# Projet_4A.net
KiCad netlist of a schematic drawn in EAGLE
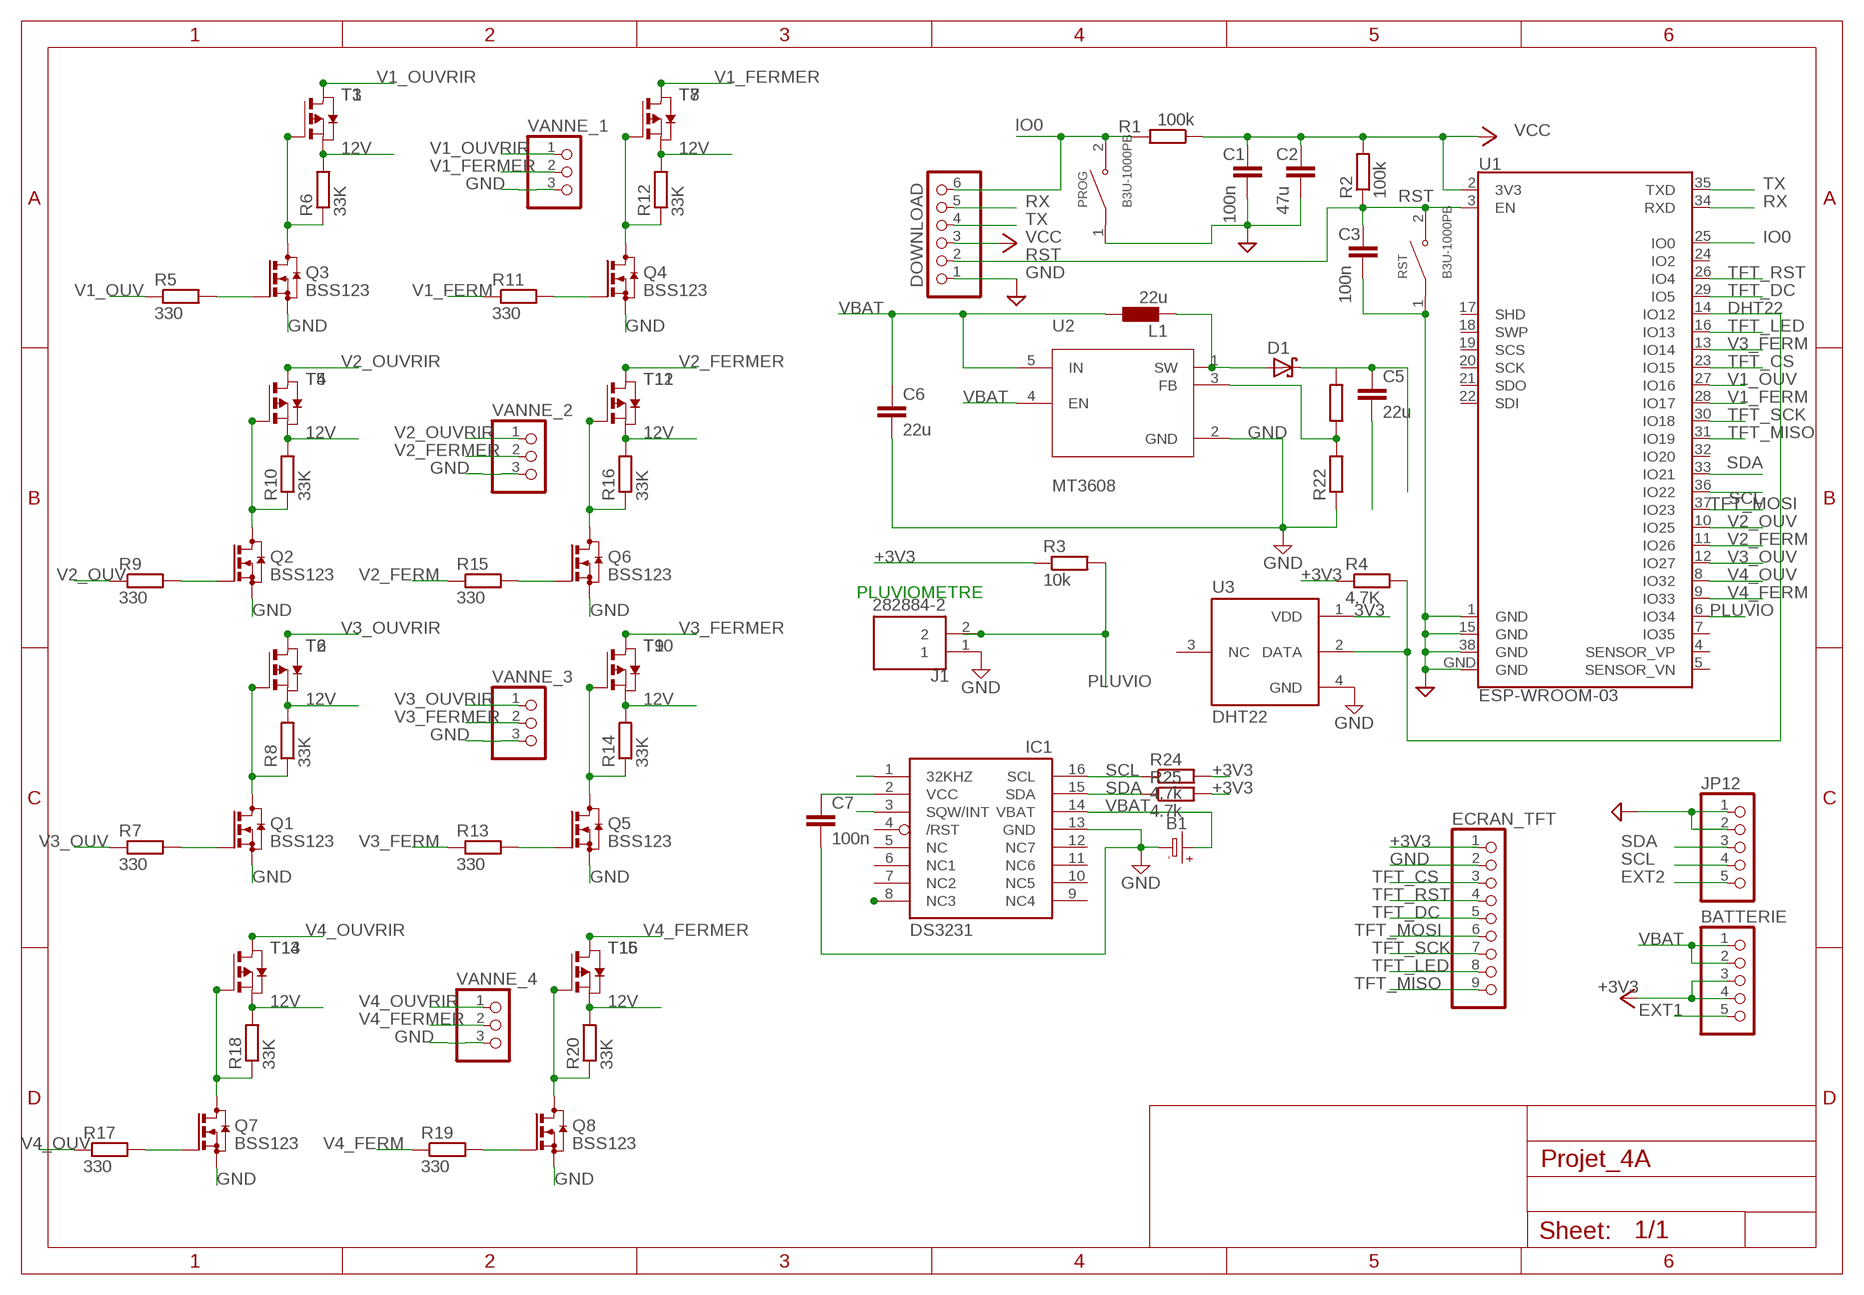
[diagram p0: schematic, sheet 1]

(export (version "E")
  (design (tool "Eeschema 10.0.6"))
  (components
    (comp (ref "B1")
      (value "BATTERYCR2032_BAT-HLD-001")
      (footprint "eagle-import:CR2032_SMT_BAT-HLD-001")
      (libsource (lib "eagle-import") (part "BATTERYCR2032_BAT-HLD-001"))
    )
    (comp (ref "BATTERIE")
      (value "PINHD-1X5S")
      (footprint "eagle-import:1X05S")
      (libsource (lib "eagle-import") (part "PINHD-1X5S"))
    )
    (comp (ref "C1")
      (value "100n")
      (footprint "eagle-import:C0805")
      (libsource (lib "eagle-import") (part "C"))
    )
    (comp (ref "C2")
      (value "47u")
      (footprint "eagle-import:C0805")
      (libsource (lib "eagle-import") (part "C"))
    )
    (comp (ref "C3")
      (value "100n")
      (footprint "eagle-import:C0805")
      (libsource (lib "eagle-import") (part "C"))
    )
    (comp (ref "C5")
      (value "22u")
      (footprint "eagle-import:C0805")
      (libsource (lib "eagle-import") (part "C"))
    )
    (comp (ref "C6")
      (value "22u")
      (footprint "eagle-import:C0805")
      (libsource (lib "eagle-import") (part "C"))
    )
    (comp (ref "C7")
      (value "100n")
      (footprint "eagle-import:C0805")
      (libsource (lib "eagle-import") (part "C"))
    )
    (comp (ref "D1")
      (value "SCHOTTKY-DIODEAG")
      (footprint "eagle-import:AG")
      (libsource (lib "eagle-import") (part "SCHOTTKY-DIODEAG"))
    )
    (comp (ref "DOWNLOAD")
      (value "PINHD-1X6S")
      (footprint "eagle-import:1X06S")
      (libsource (lib "eagle-import") (part "PINHD-1X6S"))
    )
    (comp (ref "ECRAN_TFT")
      (value "PINHD-1X9")
      (footprint "eagle-import:1X09")
      (libsource (lib "eagle-import") (part "PINHD-1X9"))
    )
    (comp (ref "IC1")
      (value "DS3231/SO")
      (footprint "eagle-import:SO16W")
      (fields (field (name "MF") "Analog Devices") (field (name "MP") "DS3231"))
      (libsource (lib "eagle-import") (part "DS3231/SO"))
    )
    (comp (ref "J1")
      (value "282884-2")
      (footprint "eagle-import:TE_282884-2")
      (fields (field (name "MF") "TE Connectivity"))
      (libsource (lib "eagle-import") (part "282884-2"))
    )
    (comp (ref "JP12")
      (value "PINHD-1X5S")
      (footprint "eagle-import:1X05S")
      (libsource (lib "eagle-import") (part "PINHD-1X5S"))
    )
    (comp (ref "L1")
      (value "22u")
      (footprint "eagle-import:0204_7")
      (libsource (lib "eagle-import") (part "L0204/7"))
    )
    (comp (ref "PROG")
      (value "B3U-1000PB")
      (footprint "eagle-import:SW_B3U-1000PB")
      (libsource (lib "eagle-import") (part "B3U-1000PB"))
    )
    (comp (ref "Q1")
      (value "BSS123")
      (footprint "eagle-import:SOT23")
      (libsource (lib "eagle-import") (part "BSS123"))
    )
    (comp (ref "Q2")
      (value "BSS123")
      (footprint "eagle-import:SOT23")
      (libsource (lib "eagle-import") (part "BSS123"))
    )
    (comp (ref "Q3")
      (value "BSS123")
      (footprint "eagle-import:SOT23")
      (libsource (lib "eagle-import") (part "BSS123"))
    )
    (comp (ref "Q4")
      (value "BSS123")
      (footprint "eagle-import:SOT23")
      (libsource (lib "eagle-import") (part "BSS123"))
    )
    (comp (ref "Q5")
      (value "BSS123")
      (footprint "eagle-import:SOT23")
      (libsource (lib "eagle-import") (part "BSS123"))
    )
    (comp (ref "Q6")
      (value "BSS123")
      (footprint "eagle-import:SOT23")
      (libsource (lib "eagle-import") (part "BSS123"))
    )
    (comp (ref "Q7")
      (value "BSS123")
      (footprint "eagle-import:SOT23")
      (libsource (lib "eagle-import") (part "BSS123"))
    )
    (comp (ref "Q8")
      (value "BSS123")
      (footprint "eagle-import:SOT23")
      (libsource (lib "eagle-import") (part "BSS123"))
    )
    (comp (ref "R1")
      (value "100k")
      (footprint "eagle-import:R1206")
      (libsource (lib "eagle-import") (part "RR1206"))
    )
    (comp (ref "R2")
      (value "100k")
      (footprint "eagle-import:R1206")
      (libsource (lib "eagle-import") (part "RR1206"))
    )
    (comp (ref "R3")
      (value "10k")
      (footprint "eagle-import:R0805")
      (libsource (lib "eagle-import") (part "R-EU_R0805"))
    )
    (comp (ref "R4")
      (value "4,7K")
      (footprint "eagle-import:0207_10")
      (libsource (lib "eagle-import") (part "R-EU_0207/10"))
    )
    (comp (ref "R5")
      (value "330")
      (footprint "eagle-import:0207_10")
      (libsource (lib "eagle-import") (part "R-EU_0207/10"))
    )
    (comp (ref "R6")
      (value "33K")
      (footprint "eagle-import:0207_10")
      (libsource (lib "eagle-import") (part "R-EU_0207/10"))
    )
    (comp (ref "R7")
      (value "330")
      (footprint "eagle-import:0207_10")
      (libsource (lib "eagle-import") (part "R-EU_0207/10"))
    )
    (comp (ref "R8")
      (value "33K")
      (footprint "eagle-import:0207_10")
      (libsource (lib "eagle-import") (part "R-EU_0207/10"))
    )
    (comp (ref "R9")
      (value "330")
      (footprint "eagle-import:0207_10")
      (libsource (lib "eagle-import") (part "R-EU_0207/10"))
    )
    (comp (ref "R10")
      (value "33K")
      (footprint "eagle-import:0207_10")
      (libsource (lib "eagle-import") (part "R-EU_0207/10"))
    )
    (comp (ref "R11")
      (value "330")
      (footprint "eagle-import:0207_10")
      (libsource (lib "eagle-import") (part "R-EU_0207/10"))
    )
    (comp (ref "R12")
      (value "33K")
      (footprint "eagle-import:0207_10")
      (libsource (lib "eagle-import") (part "R-EU_0207/10"))
    )
    (comp (ref "R13")
      (value "330")
      (footprint "eagle-import:0207_10")
      (libsource (lib "eagle-import") (part "R-EU_0207/10"))
    )
    (comp (ref "R14")
      (value "33K")
      (footprint "eagle-import:0207_10")
      (libsource (lib "eagle-import") (part "R-EU_0207/10"))
    )
    (comp (ref "R15")
      (value "330")
      (footprint "eagle-import:0207_10")
      (libsource (lib "eagle-import") (part "R-EU_0207/10"))
    )
    (comp (ref "R16")
      (value "33K")
      (footprint "eagle-import:0207_10")
      (libsource (lib "eagle-import") (part "R-EU_0207/10"))
    )
    (comp (ref "R17")
      (value "330")
      (footprint "eagle-import:0207_10")
      (libsource (lib "eagle-import") (part "R-EU_0207/10"))
    )
    (comp (ref "R18")
      (value "33K")
      (footprint "eagle-import:0207_10")
      (libsource (lib "eagle-import") (part "R-EU_0207/10"))
    )
    (comp (ref "R19")
      (value "330")
      (footprint "eagle-import:0207_10")
      (libsource (lib "eagle-import") (part "R-EU_0207/10"))
    )
    (comp (ref "R20")
      (value "33K")
      (footprint "eagle-import:0207_10")
      (libsource (lib "eagle-import") (part "R-EU_0207/10"))
    )
    (comp (ref "R22")
      (value "R-EU_0204/2V")
      (footprint "eagle-import:0204V")
      (libsource (lib "eagle-import") (part "R-EU_0204/2V"))
    )
    (comp (ref "R24")
      (value "4,7k")
      (footprint "eagle-import:0204V")
      (libsource (lib "eagle-import") (part "R-EU_0204/2V"))
    )
    (comp (ref "R25")
      (value "4.7k")
      (footprint "eagle-import:0204V")
      (libsource (lib "eagle-import") (part "R-EU_0204/2V"))
    )
    (comp (ref "RST")
      (value "B3U-1000PB")
      (footprint "eagle-import:SW_B3U-1000PB")
      (libsource (lib "eagle-import") (part "B3U-1000PB"))
    )
    (comp (ref "T1")
      (value "PMOSSOT23")
      (footprint "eagle-import:SOT-23")
      (libsource (lib "eagle-import") (part "PMOSSOT23"))
    )
    (comp (ref "T2")
      (value "PMOSSOT23")
      (footprint "eagle-import:SOT-23")
      (libsource (lib "eagle-import") (part "PMOSSOT23"))
    )
    (comp (ref "T3")
      (value "PMOSSOT23")
      (footprint "eagle-import:SOT-23")
      (libsource (lib "eagle-import") (part "PMOSSOT23"))
    )
    (comp (ref "T4")
      (value "PMOSSOT23")
      (footprint "eagle-import:SOT-23")
      (libsource (lib "eagle-import") (part "PMOSSOT23"))
    )
    (comp (ref "T5")
      (value "PMOSSOT23")
      (footprint "eagle-import:SOT-23")
      (libsource (lib "eagle-import") (part "PMOSSOT23"))
    )
    (comp (ref "T6")
      (value "PMOSSOT23")
      (footprint "eagle-import:SOT-23")
      (libsource (lib "eagle-import") (part "PMOSSOT23"))
    )
    (comp (ref "T7")
      (value "PMOSSOT23")
      (footprint "eagle-import:SOT-23")
      (libsource (lib "eagle-import") (part "PMOSSOT23"))
    )
    (comp (ref "T8")
      (value "PMOSSOT23")
      (footprint "eagle-import:SOT-23")
      (libsource (lib "eagle-import") (part "PMOSSOT23"))
    )
    (comp (ref "T9")
      (value "PMOSSOT23")
      (footprint "eagle-import:SOT-23")
      (libsource (lib "eagle-import") (part "PMOSSOT23"))
    )
    (comp (ref "T10")
      (value "PMOSSOT23")
      (footprint "eagle-import:SOT-23")
      (libsource (lib "eagle-import") (part "PMOSSOT23"))
    )
    (comp (ref "T11")
      (value "PMOSSOT23")
      (footprint "eagle-import:SOT-23")
      (libsource (lib "eagle-import") (part "PMOSSOT23"))
    )
    (comp (ref "T12")
      (value "PMOSSOT23")
      (footprint "eagle-import:SOT-23")
      (libsource (lib "eagle-import") (part "PMOSSOT23"))
    )
    (comp (ref "T13")
      (value "PMOSSOT23")
      (footprint "eagle-import:SOT-23")
      (libsource (lib "eagle-import") (part "PMOSSOT23"))
    )
    (comp (ref "T14")
      (value "PMOSSOT23")
      (footprint "eagle-import:SOT-23")
      (libsource (lib "eagle-import") (part "PMOSSOT23"))
    )
    (comp (ref "T15")
      (value "PMOSSOT23")
      (footprint "eagle-import:SOT-23")
      (libsource (lib "eagle-import") (part "PMOSSOT23"))
    )
    (comp (ref "T16")
      (value "PMOSSOT23")
      (footprint "eagle-import:SOT-23")
      (libsource (lib "eagle-import") (part "PMOSSOT23"))
    )
    (comp (ref "U1")
      (value "ESP-WROOM-03")
      (footprint "eagle-import:ESP-WROOM-03")
      (libsource (lib "eagle-import") (part "ESP-WROOM-03"))
    )
    (comp (ref "U2")
      (value "MT3608")
      (footprint "eagle-import:SOT95P280X145-6N")
      (fields (field (name "MANUFACTURER") "Aero Semi"))
      (libsource (lib "eagle-import") (part "MT3608"))
    )
    (comp (ref "U3")
      (value "DHT22")
      (footprint "eagle-import:XDCR_DHT22")
      (fields (field (name "MF") "Aosong Electronics"))
      (libsource (lib "eagle-import") (part "DHT22"))
    )
    (comp (ref "VANNE_1")
      (value "PINHD-1X3")
      (footprint "eagle-import:1X03")
      (libsource (lib "eagle-import") (part "PINHD-1X3"))
    )
    (comp (ref "VANNE_2")
      (value "PINHD-1X3")
      (footprint "eagle-import:1X03")
      (libsource (lib "eagle-import") (part "PINHD-1X3"))
    )
    (comp (ref "VANNE_3")
      (value "PINHD-1X3")
      (footprint "eagle-import:1X03")
      (libsource (lib "eagle-import") (part "PINHD-1X3"))
    )
    (comp (ref "VANNE_4")
      (value "PINHD-1X3")
      (footprint "eagle-import:1X03")
      (libsource (lib "eagle-import") (part "PINHD-1X3"))
    )
  )
  (nets
    (net (code "1") (name "+3V3") (class "Default")
      (node (ref "BATTERIE") (pin "3") (pinfunction "3_3") (pintype "passive"))
      (node (ref "BATTERIE") (pin "4") (pinfunction "4_4") (pintype "passive"))
      (node (ref "C7") (pin "1") (pinfunction "1_1") (pintype "passive"))
      (node (ref "ECRAN_TFT") (pin "1") (pinfunction "1_1") (pintype "passive"))
      (node (ref "IC1") (pin "2") (pinfunction "VCC_2") (pintype "power_in"))
      (node (ref "R24") (pin "2") (pinfunction "2_2") (pintype "passive"))
      (node (ref "R25") (pin "2") (pinfunction "2_2") (pintype "passive"))
      (node (ref "R3") (pin "1") (pinfunction "1_1") (pintype "passive"))
      (node (ref "R4") (pin "1") (pinfunction "1_1") (pintype "passive"))
    )
    (net (code "2") (name "/3V3") (class "Default")
      (node (ref "U3") (pin "1") (pinfunction "VDD_1") (pintype "power_in"))
    )
    (net (code "3") (name "/12V") (class "Default")
      (node (ref "C5") (pin "1") (pinfunction "1_1") (pintype "passive"))
      (node (ref "D1") (pin "C") (pinfunction "C_C") (pintype "passive"))
      (node (ref "R10") (pin "2") (pinfunction "2_2") (pintype "passive"))
      (node (ref "R12") (pin "2") (pinfunction "2_2") (pintype "passive"))
      (node (ref "R14") (pin "2") (pinfunction "2_2") (pintype "passive"))
      (node (ref "R16") (pin "2") (pinfunction "2_2") (pintype "passive"))
      (node (ref "R18") (pin "2") (pinfunction "2_2") (pintype "passive"))
      (node (ref "R20") (pin "2") (pinfunction "2_2") (pintype "passive"))
      (node (ref "R6") (pin "2") (pinfunction "2_2") (pintype "passive"))
      (node (ref "R8") (pin "2") (pinfunction "2_2") (pintype "passive"))
      (node (ref "T1") (pin "2") (pinfunction "S_2") (pintype "passive"))
      (node (ref "T10") (pin "2") (pinfunction "S_2") (pintype "passive"))
      (node (ref "T11") (pin "2") (pinfunction "S_2") (pintype "passive"))
      (node (ref "T12") (pin "2") (pinfunction "S_2") (pintype "passive"))
      (node (ref "T13") (pin "2") (pinfunction "S_2") (pintype "passive"))
      (node (ref "T14") (pin "2") (pinfunction "S_2") (pintype "passive"))
      (node (ref "T15") (pin "2") (pinfunction "S_2") (pintype "passive"))
      (node (ref "T16") (pin "2") (pinfunction "S_2") (pintype "passive"))
      (node (ref "T2") (pin "2") (pinfunction "S_2") (pintype "passive"))
      (node (ref "T3") (pin "2") (pinfunction "S_2") (pintype "passive"))
      (node (ref "T4") (pin "2") (pinfunction "S_2") (pintype "passive"))
      (node (ref "T5") (pin "2") (pinfunction "S_2") (pintype "passive"))
      (node (ref "T6") (pin "2") (pinfunction "S_2") (pintype "passive"))
      (node (ref "T7") (pin "2") (pinfunction "S_2") (pintype "passive"))
      (node (ref "T8") (pin "2") (pinfunction "S_2") (pintype "passive"))
      (node (ref "T9") (pin "2") (pinfunction "S_2") (pintype "passive"))
    )
    (net (code "4") (name "/DHT22") (class "Default")
      (node (ref "R4") (pin "2") (pinfunction "2_2") (pintype "passive"))
      (node (ref "U1") (pin "14") (pinfunction "IO12_14") (pintype "bidirectional"))
      (node (ref "U3") (pin "2") (pinfunction "DATA_2") (pintype "bidirectional"))
    )
    (net (code "5") (name "/EXT1") (class "Default")
      (node (ref "BATTERIE") (pin "5") (pinfunction "5_5") (pintype "passive"))
    )
    (net (code "6") (name "/EXT2") (class "Default")
      (node (ref "JP12") (pin "5") (pinfunction "5_5") (pintype "passive"))
    )
    (net (code "7") (name "/IO0") (class "Default")
      (node (ref "DOWNLOAD") (pin "6") (pinfunction "6_6") (pintype "passive"))
      (node (ref "PROG") (pin "2") (pinfunction "2_2") (pintype "passive"))
      (node (ref "R1") (pin "2") (pinfunction "2_2") (pintype "passive"))
      (node (ref "U1") (pin "25") (pinfunction "IO0_25") (pintype "bidirectional"))
    )
    (net (code "8") (name "/PLUVIO") (class "Default")
      (node (ref "J1") (pin "2") (pinfunction "2_2") (pintype "passive"))
      (node (ref "R3") (pin "2") (pinfunction "2_2") (pintype "passive"))
      (node (ref "U1") (pin "6") (pinfunction "IO34_6") (pintype "bidirectional"))
    )
    (net (code "9") (name "/RST") (class "Default")
      (node (ref "C3") (pin "1") (pinfunction "1_1") (pintype "passive"))
      (node (ref "DOWNLOAD") (pin "2") (pinfunction "2_2") (pintype "passive"))
      (node (ref "R2") (pin "1") (pinfunction "1_1") (pintype "passive"))
      (node (ref "RST") (pin "2") (pinfunction "2_2") (pintype "passive"))
      (node (ref "U1") (pin "3") (pinfunction "EN_3") (pintype "bidirectional"))
    )
    (net (code "10") (name "/RX") (class "Default")
      (node (ref "DOWNLOAD") (pin "5") (pinfunction "5_5") (pintype "passive"))
      (node (ref "U1") (pin "34") (pinfunction "RXD_34") (pintype "bidirectional"))
    )
    (net (code "11") (name "/SCL") (class "Default")
      (node (ref "IC1") (pin "16") (pinfunction "SCL_16") (pintype "bidirectional"))
      (node (ref "JP12") (pin "4") (pinfunction "4_4") (pintype "passive"))
      (node (ref "R24") (pin "1") (pinfunction "1_1") (pintype "passive"))
      (node (ref "U1") (pin "36") (pinfunction "IO22_36") (pintype "bidirectional"))
    )
    (net (code "12") (name "/SDA") (class "Default")
      (node (ref "IC1") (pin "15") (pinfunction "SDA_15") (pintype "bidirectional"))
      (node (ref "JP12") (pin "3") (pinfunction "3_3") (pintype "passive"))
      (node (ref "R25") (pin "1") (pinfunction "1_1") (pintype "passive"))
      (node (ref "U1") (pin "33") (pinfunction "IO21_33") (pintype "bidirectional"))
    )
    (net (code "13") (name "/TFT_CS") (class "Default")
      (node (ref "ECRAN_TFT") (pin "3") (pinfunction "3_3") (pintype "passive"))
      (node (ref "U1") (pin "23") (pinfunction "IO15_23") (pintype "bidirectional"))
    )
    (net (code "14") (name "/TFT_DC") (class "Default")
      (node (ref "ECRAN_TFT") (pin "5") (pinfunction "5_5") (pintype "passive"))
      (node (ref "U1") (pin "29") (pinfunction "IO5_29") (pintype "bidirectional"))
    )
    (net (code "15") (name "/TFT_LED") (class "Default")
      (node (ref "ECRAN_TFT") (pin "8") (pinfunction "8_8") (pintype "passive"))
      (node (ref "U1") (pin "16") (pinfunction "IO13_16") (pintype "bidirectional"))
    )
    (net (code "16") (name "/TFT_MISO") (class "Default")
      (node (ref "ECRAN_TFT") (pin "9") (pinfunction "9_9") (pintype "passive"))
      (node (ref "U1") (pin "31") (pinfunction "IO19_31") (pintype "bidirectional"))
    )
    (net (code "17") (name "/TFT_MOSI") (class "Default")
      (node (ref "ECRAN_TFT") (pin "6") (pinfunction "6_6") (pintype "passive"))
      (node (ref "U1") (pin "37") (pinfunction "IO23_37") (pintype "bidirectional"))
    )
    (net (code "18") (name "/TFT_RST") (class "Default")
      (node (ref "ECRAN_TFT") (pin "4") (pinfunction "4_4") (pintype "passive"))
      (node (ref "U1") (pin "26") (pinfunction "IO4_26") (pintype "bidirectional"))
    )
    (net (code "19") (name "/TFT_SCK") (class "Default")
      (node (ref "ECRAN_TFT") (pin "7") (pinfunction "7_7") (pintype "passive"))
      (node (ref "U1") (pin "30") (pinfunction "IO18_30") (pintype "bidirectional"))
    )
    (net (code "20") (name "/TX") (class "Default")
      (node (ref "DOWNLOAD") (pin "4") (pinfunction "4_4") (pintype "passive"))
      (node (ref "U1") (pin "35") (pinfunction "TXD_35") (pintype "bidirectional"))
    )
    (net (code "21") (name "/V1_FERM") (class "Default")
      (node (ref "R11") (pin "1") (pinfunction "1_1") (pintype "passive"))
      (node (ref "U1") (pin "28") (pinfunction "IO17_28") (pintype "bidirectional"))
    )
    (net (code "22") (name "/V1_FERMER") (class "Default")
      (node (ref "T7") (pin "1") (pinfunction "D_1") (pintype "passive"))
      (node (ref "T8") (pin "1") (pinfunction "D_1") (pintype "passive"))
      (node (ref "VANNE_1") (pin "2") (pinfunction "2_2") (pintype "passive"))
    )
    (net (code "23") (name "/V1_OUV") (class "Default")
      (node (ref "R5") (pin "1") (pinfunction "1_1") (pintype "passive"))
      (node (ref "U1") (pin "27") (pinfunction "IO16_27") (pintype "bidirectional"))
    )
    (net (code "24") (name "/V1_OUVRIR") (class "Default")
      (node (ref "T1") (pin "1") (pinfunction "D_1") (pintype "passive"))
      (node (ref "T3") (pin "1") (pinfunction "D_1") (pintype "passive"))
      (node (ref "VANNE_1") (pin "1") (pinfunction "1_1") (pintype "passive"))
    )
    (net (code "25") (name "/V2_FERM") (class "Default")
      (node (ref "R15") (pin "1") (pinfunction "1_1") (pintype "passive"))
      (node (ref "U1") (pin "11") (pinfunction "IO26_11") (pintype "bidirectional"))
    )
    (net (code "26") (name "/V2_FERMER") (class "Default")
      (node (ref "T11") (pin "1") (pinfunction "D_1") (pintype "passive"))
      (node (ref "T12") (pin "1") (pinfunction "D_1") (pintype "passive"))
      (node (ref "VANNE_2") (pin "2") (pinfunction "2_2") (pintype "passive"))
    )
    (net (code "27") (name "/V2_OUV") (class "Default")
      (node (ref "R9") (pin "1") (pinfunction "1_1") (pintype "passive"))
      (node (ref "U1") (pin "10") (pinfunction "IO25_10") (pintype "bidirectional"))
    )
    (net (code "28") (name "/V2_OUVRIR") (class "Default")
      (node (ref "T4") (pin "1") (pinfunction "D_1") (pintype "passive"))
      (node (ref "T5") (pin "1") (pinfunction "D_1") (pintype "passive"))
      (node (ref "VANNE_2") (pin "1") (pinfunction "1_1") (pintype "passive"))
    )
    (net (code "29") (name "/V3_FERM") (class "Default")
      (node (ref "R13") (pin "1") (pinfunction "1_1") (pintype "passive"))
      (node (ref "U1") (pin "13") (pinfunction "IO14_13") (pintype "bidirectional"))
    )
    (net (code "30") (name "/V3_FERMER") (class "Default")
      (node (ref "T10") (pin "1") (pinfunction "D_1") (pintype "passive"))
      (node (ref "T9") (pin "1") (pinfunction "D_1") (pintype "passive"))
      (node (ref "VANNE_3") (pin "2") (pinfunction "2_2") (pintype "passive"))
    )
    (net (code "31") (name "/V3_OUV") (class "Default")
      (node (ref "R7") (pin "1") (pinfunction "1_1") (pintype "passive"))
      (node (ref "U1") (pin "12") (pinfunction "IO27_12") (pintype "bidirectional"))
    )
    (net (code "32") (name "/V3_OUVRIR") (class "Default")
      (node (ref "T2") (pin "1") (pinfunction "D_1") (pintype "passive"))
      (node (ref "T6") (pin "1") (pinfunction "D_1") (pintype "passive"))
      (node (ref "VANNE_3") (pin "1") (pinfunction "1_1") (pintype "passive"))
    )
    (net (code "33") (name "/V4_FERM") (class "Default")
      (node (ref "R19") (pin "1") (pinfunction "1_1") (pintype "passive"))
      (node (ref "U1") (pin "9") (pinfunction "IO33_9") (pintype "bidirectional"))
    )
    (net (code "34") (name "/V4_FERMER") (class "Default")
      (node (ref "T15") (pin "1") (pinfunction "D_1") (pintype "passive"))
      (node (ref "T16") (pin "1") (pinfunction "D_1") (pintype "passive"))
      (node (ref "VANNE_4") (pin "2") (pinfunction "2_2") (pintype "passive"))
    )
    (net (code "35") (name "/V4_OUV") (class "Default")
      (node (ref "R17") (pin "1") (pinfunction "1_1") (pintype "passive"))
      (node (ref "U1") (pin "8") (pinfunction "IO32_8") (pintype "bidirectional"))
    )
    (net (code "36") (name "/V4_OUVRIR") (class "Default")
      (node (ref "T13") (pin "1") (pinfunction "D_1") (pintype "passive"))
      (node (ref "T14") (pin "1") (pinfunction "D_1") (pintype "passive"))
      (node (ref "VANNE_4") (pin "1") (pinfunction "1_1") (pintype "passive"))
    )
    (net (code "37") (name "/VBAT") (class "Default")
      (node (ref "B1") (pin "+$1") (pinfunction "+_+$1") (pintype "passive"))
      (node (ref "B1") (pin "+$2") (pinfunction "+_+$2") (pintype "passive"))
      (node (ref "BATTERIE") (pin "1") (pinfunction "1_1") (pintype "passive"))
      (node (ref "BATTERIE") (pin "2") (pinfunction "2_2") (pintype "passive"))
      (node (ref "C6") (pin "1") (pinfunction "1_1") (pintype "passive"))
      (node (ref "IC1") (pin "14") (pinfunction "VBAT_14") (pintype "power_in"))
      (node (ref "L1") (pin "1") (pinfunction "1_1") (pintype "passive"))
      (node (ref "U2") (pin "4") (pinfunction "EN_4") (pintype "input"))
      (node (ref "U2") (pin "5") (pinfunction "IN_5") (pintype "input"))
    )
    (net (code "38") (name "GND") (class "Default")
      (node (ref "B1") (pin "-") (pinfunction "-_-") (pintype "passive"))
      (node (ref "C1") (pin "2") (pinfunction "2_2") (pintype "passive"))
      (node (ref "C2") (pin "2") (pinfunction "2_2") (pintype "passive"))
      (node (ref "C3") (pin "2") (pinfunction "2_2") (pintype "passive"))
      (node (ref "C6") (pin "2") (pinfunction "2_2") (pintype "passive"))
      (node (ref "C7") (pin "2") (pinfunction "2_2") (pintype "passive"))
      (node (ref "DOWNLOAD") (pin "1") (pinfunction "1_1") (pintype "passive"))
      (node (ref "ECRAN_TFT") (pin "2") (pinfunction "2_2") (pintype "passive"))
      (node (ref "IC1") (pin "13") (pinfunction "GND_13") (pintype "power_in"))
      (node (ref "J1") (pin "1") (pinfunction "1_1") (pintype "passive"))
      (node (ref "JP12") (pin "1") (pinfunction "1_1") (pintype "passive"))
      (node (ref "JP12") (pin "2") (pinfunction "2_2") (pintype "passive"))
      (node (ref "PROG") (pin "1") (pinfunction "1_1") (pintype "passive"))
      (node (ref "Q1") (pin "2") (pinfunction "S_2") (pintype "passive"))
      (node (ref "Q2") (pin "2") (pinfunction "S_2") (pintype "passive"))
      (node (ref "Q3") (pin "2") (pinfunction "S_2") (pintype "passive"))
      (node (ref "Q4") (pin "2") (pinfunction "S_2") (pintype "passive"))
      (node (ref "Q5") (pin "2") (pinfunction "S_2") (pintype "passive"))
      (node (ref "Q6") (pin "2") (pinfunction "S_2") (pintype "passive"))
      (node (ref "Q7") (pin "2") (pinfunction "S_2") (pintype "passive"))
      (node (ref "Q8") (pin "2") (pinfunction "S_2") (pintype "passive"))
      (node (ref "R22") (pin "1") (pinfunction "1_1") (pintype "passive"))
      (node (ref "RST") (pin "1") (pinfunction "1_1") (pintype "passive"))
      (node (ref "U1") (pin "1") (pinfunction "GND_1") (pintype "bidirectional"))
      (node (ref "U1") (pin "15") (pinfunction "GND_15") (pintype "bidirectional"))
      (node (ref "U1") (pin "38") (pinfunction "GND_38") (pintype "bidirectional"))
      (node (ref "U1") (pin "GND") (pinfunction "GND_GND") (pintype "bidirectional"))
      (node (ref "U2") (pin "2") (pinfunction "GND_2") (pintype "power_in"))
      (node (ref "U3") (pin "4") (pinfunction "GND_4") (pintype "power_in"))
      (node (ref "VANNE_1") (pin "3") (pinfunction "3_3") (pintype "passive"))
      (node (ref "VANNE_2") (pin "3") (pinfunction "3_3") (pintype "passive"))
      (node (ref "VANNE_3") (pin "3") (pinfunction "3_3") (pintype "passive"))
      (node (ref "VANNE_4") (pin "3") (pinfunction "3_3") (pintype "passive"))
    )
    (net (code "39") (name "Net-(Q1-D)") (class "Default")
      (node (ref "Q1") (pin "3") (pinfunction "D_3") (pintype "passive"))
      (node (ref "R8") (pin "1") (pinfunction "1_1") (pintype "passive"))
      (node (ref "T2") (pin "3") (pinfunction "G_3") (pintype "passive"))
      (node (ref "T6") (pin "3") (pinfunction "G_3") (pintype "passive"))
    )
    (net (code "40") (name "Net-(Q1-G)") (class "Default")
      (node (ref "Q1") (pin "1") (pinfunction "G_1") (pintype "passive"))
      (node (ref "R7") (pin "2") (pinfunction "2_2") (pintype "passive"))
    )
    (net (code "41") (name "Net-(Q2-D)") (class "Default")
      (node (ref "Q2") (pin "3") (pinfunction "D_3") (pintype "passive"))
      (node (ref "R10") (pin "1") (pinfunction "1_1") (pintype "passive"))
      (node (ref "T4") (pin "3") (pinfunction "G_3") (pintype "passive"))
      (node (ref "T5") (pin "3") (pinfunction "G_3") (pintype "passive"))
    )
    (net (code "42") (name "Net-(Q2-G)") (class "Default")
      (node (ref "Q2") (pin "1") (pinfunction "G_1") (pintype "passive"))
      (node (ref "R9") (pin "2") (pinfunction "2_2") (pintype "passive"))
    )
    (net (code "43") (name "Net-(Q3-D)") (class "Default")
      (node (ref "Q3") (pin "3") (pinfunction "D_3") (pintype "passive"))
      (node (ref "R6") (pin "1") (pinfunction "1_1") (pintype "passive"))
      (node (ref "T1") (pin "3") (pinfunction "G_3") (pintype "passive"))
      (node (ref "T3") (pin "3") (pinfunction "G_3") (pintype "passive"))
    )
    (net (code "44") (name "Net-(Q3-G)") (class "Default")
      (node (ref "Q3") (pin "1") (pinfunction "G_1") (pintype "passive"))
      (node (ref "R5") (pin "2") (pinfunction "2_2") (pintype "passive"))
    )
    (net (code "45") (name "Net-(Q4-D)") (class "Default")
      (node (ref "Q4") (pin "3") (pinfunction "D_3") (pintype "passive"))
      (node (ref "R12") (pin "1") (pinfunction "1_1") (pintype "passive"))
      (node (ref "T7") (pin "3") (pinfunction "G_3") (pintype "passive"))
      (node (ref "T8") (pin "3") (pinfunction "G_3") (pintype "passive"))
    )
    (net (code "46") (name "Net-(Q4-G)") (class "Default")
      (node (ref "Q4") (pin "1") (pinfunction "G_1") (pintype "passive"))
      (node (ref "R11") (pin "2") (pinfunction "2_2") (pintype "passive"))
    )
    (net (code "47") (name "Net-(Q5-D)") (class "Default")
      (node (ref "Q5") (pin "3") (pinfunction "D_3") (pintype "passive"))
      (node (ref "R14") (pin "1") (pinfunction "1_1") (pintype "passive"))
      (node (ref "T10") (pin "3") (pinfunction "G_3") (pintype "passive"))
      (node (ref "T9") (pin "3") (pinfunction "G_3") (pintype "passive"))
    )
    (net (code "48") (name "Net-(Q5-G)") (class "Default")
      (node (ref "Q5") (pin "1") (pinfunction "G_1") (pintype "passive"))
      (node (ref "R13") (pin "2") (pinfunction "2_2") (pintype "passive"))
    )
    (net (code "49") (name "Net-(Q6-D)") (class "Default")
      (node (ref "Q6") (pin "3") (pinfunction "D_3") (pintype "passive"))
      (node (ref "R16") (pin "1") (pinfunction "1_1") (pintype "passive"))
      (node (ref "T11") (pin "3") (pinfunction "G_3") (pintype "passive"))
      (node (ref "T12") (pin "3") (pinfunction "G_3") (pintype "passive"))
    )
    (net (code "50") (name "Net-(Q6-G)") (class "Default")
      (node (ref "Q6") (pin "1") (pinfunction "G_1") (pintype "passive"))
      (node (ref "R15") (pin "2") (pinfunction "2_2") (pintype "passive"))
    )
    (net (code "51") (name "Net-(Q7-D)") (class "Default")
      (node (ref "Q7") (pin "3") (pinfunction "D_3") (pintype "passive"))
      (node (ref "R18") (pin "1") (pinfunction "1_1") (pintype "passive"))
      (node (ref "T13") (pin "3") (pinfunction "G_3") (pintype "passive"))
      (node (ref "T14") (pin "3") (pinfunction "G_3") (pintype "passive"))
    )
    (net (code "52") (name "Net-(Q7-G)") (class "Default")
      (node (ref "Q7") (pin "1") (pinfunction "G_1") (pintype "passive"))
      (node (ref "R17") (pin "2") (pinfunction "2_2") (pintype "passive"))
    )
    (net (code "53") (name "Net-(Q8-D)") (class "Default")
      (node (ref "Q8") (pin "3") (pinfunction "D_3") (pintype "passive"))
      (node (ref "R20") (pin "1") (pinfunction "1_1") (pintype "passive"))
      (node (ref "T15") (pin "3") (pinfunction "G_3") (pintype "passive"))
      (node (ref "T16") (pin "3") (pinfunction "G_3") (pintype "passive"))
    )
    (net (code "54") (name "Net-(Q8-G)") (class "Default")
      (node (ref "Q8") (pin "1") (pinfunction "G_1") (pintype "passive"))
      (node (ref "R19") (pin "2") (pinfunction "2_2") (pintype "passive"))
    )
    (net (code "55") (name "Net-(U2-FB)") (class "Default")
      (node (ref "R22") (pin "2") (pinfunction "2_2") (pintype "passive"))
      (node (ref "U2") (pin "3") (pinfunction "FB_3") (pintype "input"))
    )
    (net (code "56") (name "Net-(U2-SW)") (class "Default")
      (node (ref "D1") (pin "A") (pinfunction "A_A") (pintype "passive"))
      (node (ref "L1") (pin "2") (pinfunction "2_2") (pintype "passive"))
      (node (ref "U2") (pin "1") (pinfunction "SW_1") (pintype "output"))
    )
    (net (code "57") (name "VCC") (class "Default")
      (node (ref "C1") (pin "1") (pinfunction "1_1") (pintype "passive"))
      (node (ref "C2") (pin "1") (pinfunction "1_1") (pintype "passive"))
      (node (ref "DOWNLOAD") (pin "3") (pinfunction "3_3") (pintype "passive"))
      (node (ref "R1") (pin "1") (pinfunction "1_1") (pintype "passive"))
      (node (ref "R2") (pin "2") (pinfunction "2_2") (pintype "passive"))
      (node (ref "U1") (pin "2") (pinfunction "3V3_2") (pintype "bidirectional"))
    )
    (net (code "58") (name "unconnected-(C5-Pad2)") (class "Default")
      (node (ref "C5") (pin "2") (pinfunction "2_2") (pintype "passive"))
    )
    (net (code "59") (name "unconnected-(IC1-32KHZ-Pad1)") (class "Default")
      (node (ref "IC1") (pin "1") (pinfunction "32KHZ_1") (pintype "output"))
    )
    (net (code "60") (name "unconnected-(IC1-NC-Pad5)") (class "Default")
      (node (ref "IC1") (pin "5") (pinfunction "NC_5") (pintype "no_connect"))
    )
    (net (code "61") (name "unconnected-(IC1-NC1-Pad6)") (class "Default")
      (node (ref "IC1") (pin "6") (pinfunction "NC1_6") (pintype "no_connect"))
    )
    (net (code "62") (name "unconnected-(IC1-NC2-Pad7)") (class "Default")
      (node (ref "IC1") (pin "7") (pinfunction "NC2_7") (pintype "no_connect"))
    )
    (net (code "63") (name "unconnected-(IC1-NC3-Pad8)") (class "Default")
      (node (ref "IC1") (pin "8") (pinfunction "NC3_8") (pintype "no_connect"))
    )
    (net (code "64") (name "unconnected-(IC1-NC4-Pad9)") (class "Default")
      (node (ref "IC1") (pin "9") (pinfunction "NC4_9") (pintype "no_connect"))
    )
    (net (code "65") (name "unconnected-(IC1-NC5-Pad10)") (class "Default")
      (node (ref "IC1") (pin "10") (pinfunction "NC5_10") (pintype "no_connect"))
    )
    (net (code "66") (name "unconnected-(IC1-NC6-Pad11)") (class "Default")
      (node (ref "IC1") (pin "11") (pinfunction "NC6_11") (pintype "no_connect"))
    )
    (net (code "67") (name "unconnected-(IC1-NC7-Pad12)") (class "Default")
      (node (ref "IC1") (pin "12") (pinfunction "NC7_12") (pintype "no_connect"))
    )
    (net (code "68") (name "unconnected-(IC1-SQW{slash}INT-Pad3)") (class "Default")
      (node (ref "IC1") (pin "3") (pinfunction "SQW/INT_3") (pintype "output"))
    )
    (net (code "69") (name "unconnected-(IC1-{slash}RST-Pad4)") (class "Default")
      (node (ref "IC1") (pin "4") (pinfunction "/RST_4") (pintype "passive"))
    )
    (net (code "70") (name "unconnected-(U1-IO2-Pad24)") (class "Default")
      (node (ref "U1") (pin "24") (pinfunction "IO2_24") (pintype "bidirectional"))
    )
    (net (code "71") (name "unconnected-(U1-IO20-Pad32)") (class "Default")
      (node (ref "U1") (pin "32") (pinfunction "IO20_32") (pintype "bidirectional"))
    )
    (net (code "72") (name "unconnected-(U1-IO35-Pad7)") (class "Default")
      (node (ref "U1") (pin "7") (pinfunction "IO35_7") (pintype "bidirectional"))
    )
    (net (code "73") (name "unconnected-(U1-SCK-Pad20)") (class "Default")
      (node (ref "U1") (pin "20") (pinfunction "SCK_20") (pintype "bidirectional"))
    )
    (net (code "74") (name "unconnected-(U1-SCS-Pad19)") (class "Default")
      (node (ref "U1") (pin "19") (pinfunction "SCS_19") (pintype "bidirectional"))
    )
    (net (code "75") (name "unconnected-(U1-SDI-Pad22)") (class "Default")
      (node (ref "U1") (pin "22") (pinfunction "SDI_22") (pintype "bidirectional"))
    )
    (net (code "76") (name "unconnected-(U1-SDO-Pad21)") (class "Default")
      (node (ref "U1") (pin "21") (pinfunction "SDO_21") (pintype "bidirectional"))
    )
    (net (code "77") (name "unconnected-(U1-SENSOR_VN-Pad5)") (class "Default")
      (node (ref "U1") (pin "5") (pinfunction "SENSOR_VN_5") (pintype "bidirectional"))
    )
    (net (code "78") (name "unconnected-(U1-SENSOR_VP-Pad4)") (class "Default")
      (node (ref "U1") (pin "4") (pinfunction "SENSOR_VP_4") (pintype "bidirectional"))
    )
    (net (code "79") (name "unconnected-(U1-SHD-Pad17)") (class "Default")
      (node (ref "U1") (pin "17") (pinfunction "SHD_17") (pintype "bidirectional"))
    )
    (net (code "80") (name "unconnected-(U1-SWP-Pad18)") (class "Default")
      (node (ref "U1") (pin "18") (pinfunction "SWP_18") (pintype "bidirectional"))
    )
    (net (code "81") (name "unconnected-(U3-NC-Pad3)") (class "Default")
      (node (ref "U3") (pin "3") (pinfunction "NC_3") (pintype "no_connect"))
    )
  )
)
